# peripherals.net
KiCad netlist of a schematic drawn in Altium Designer
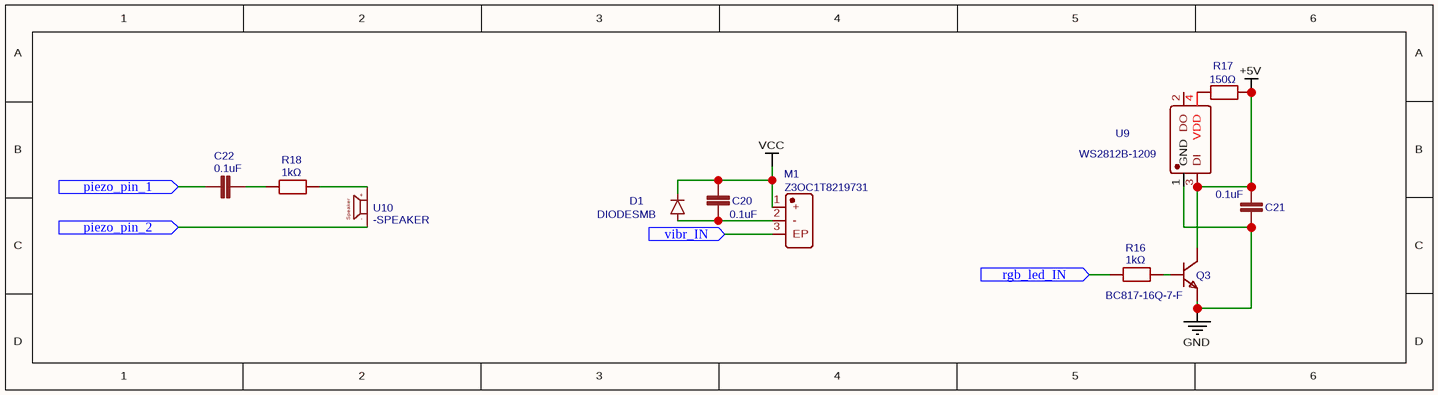
[diagram p0: peripherals.schdoc]

(export (version "E")
  (design (tool "Eeschema 10.0.6"))
  (components
    (comp (ref "C20")
      (value "0.1uF")
      (description "CAP-00810")
      (fields (field (name "CONTRIBUTOR") "SparkFun"))
      (libsource (lib "altium-import") (part "root_0_0.1uF_"))
    )
    (comp (ref "C21")
      (value "0.1uF")
      (description "CAP-00810")
      (fields (field (name "CONTRIBUTOR") "SparkFun"))
      (libsource (lib "altium-import") (part "root_0_0.1uF_"))
    )
    (comp (ref "C22")
      (value "0.1uF")
      (description "CAP-00810")
      (fields (field (name "CONTRIBUTOR") "SparkFun"))
      (libsource (lib "altium-import") (part "root_1_0.1uF_"))
    )
    (comp (ref "D1")
      (value "DIODESMB")
      (description "Diode")
      (fields (field (name "CONTRIBUTOR") "SparkFun"))
      (libsource (lib "altium-import") (part "root_1_DIODESMB_"))
    )
    (comp (ref "M1")
      (value "Z3OC1T8219731")
      (fields (field (name "BOM_SUPPLIER PART") "C2894731") (field (name "CONTRIBUTOR") "LCSC"))
      (libsource (lib "altium-import") (part "root_0_Z3OC1T8219731_"))
    )
    (comp (ref "Q3")
      (value "BC817-16Q-7-F")
      (fields (field (name "BOM_SUPPLIER PART") "C526459") (field (name "CONTRIBUTOR") "LCSC"))
      (libsource (lib "altium-import") (part "root_0_BC817-16Q-7-F_"))
    )
    (comp (ref "R16")
      (value "1kΩ")
      (fields
        (field (name "BOM_SUPPLIER PART") "C525388")
        (field (name "BOM_MANUFACTURER PART") "TCTR0603F47K0F3960T")
        (field (name "CONTRIBUTOR") "LCSC")
      )
      (libsource (lib "altium-import") (part "root_2_1kΩ_"))
    )
    (comp (ref "R17")
      (value "150Ω")
      (fields
        (field (name "BOM_SUPPLIER PART") "C525388")
        (field (name "BOM_MANUFACTURER PART") "TCTR0603F47K0F3960T")
        (field (name "CONTRIBUTOR") "LCSC")
      )
      (libsource (lib "altium-import") (part "root_0_150Ω_"))
    )
    (comp (ref "R18")
      (value "1kΩ")
      (fields
        (field (name "BOM_SUPPLIER PART") "C525388")
        (field (name "BOM_MANUFACTURER PART") "TCTR0603F47K0F3960T")
        (field (name "CONTRIBUTOR") "LCSC")
      )
      (libsource (lib "altium-import") (part "root_2_1kΩ_"))
    )
    (comp (ref "U9")
      (value "WS2812B-1209")
      (fields (field (name "BOM_SUPPLIER PART") "C2835111") (field (name "CONTRIBUTOR") "LCSC"))
      (libsource (lib "altium-import") (part "root_1_WS2812B-1209_"))
    )
    (comp (ref "U10") (value "-SPEAKER") (libsource (lib "altium-import") (part "root_1_-SPEAKER_")))
  )
  (nets
    (net (code "1") (name "+5V") (class "Default")
      (node (ref "C21") (pin "1") (pinfunction "1_1") (pintype "passive"))
      (node (ref "Q3") (pin "3") (pinfunction "C_3") (pintype "passive"))
      (node (ref "R17") (pin "2") (pinfunction "2_2") (pintype "passive"))
      (node (ref "U9") (pin "3") (pinfunction "DI_3") (pintype "passive"))
    )
    (net (code "2") (name "/piezo_pin_1") (class "Default")
      (node (ref "C22") (pin "1") (pinfunction "1_1") (pintype "passive"))
    )
    (net (code "3") (name "/piezo_pin_2") (class "Default")
      (node (ref "U10") (pin "NEG") (pinfunction "NEG_NEG") (pintype "passive"))
    )
    (net (code "4") (name "/rgb_led_IN") (class "Default")
      (node (ref "R16") (pin "2") (pinfunction "2_2") (pintype "passive"))
    )
    (net (code "5") (name "/vibr_IN") (class "Default")
      (node (ref "M1") (pin "3") (pinfunction "EP_3") (pintype "passive"))
    )
    (net (code "6") (name "GND") (class "Default")
      (node (ref "C21") (pin "2") (pinfunction "2_2") (pintype "passive"))
      (node (ref "Q3") (pin "2") (pinfunction "E_2") (pintype "passive"))
      (node (ref "U9") (pin "1") (pinfunction "GND_1") (pintype "passive"))
    )
    (net (code "7") (name "Net-(C22-Pad2)") (class "Default")
      (node (ref "C22") (pin "2") (pinfunction "2_2") (pintype "passive"))
      (node (ref "R18") (pin "2") (pinfunction "2_2") (pintype "passive"))
    )
    (net (code "8") (name "Net-(M1--)") (class "Default")
      (node (ref "C20") (pin "2") (pinfunction "2_2") (pintype "passive"))
      (node (ref "D1") (pin "A") (pinfunction "A_A") (pintype "passive"))
      (node (ref "M1") (pin "2") (pinfunction "-_2") (pintype "passive"))
    )
    (net (code "9") (name "Net-(Q3-B)") (class "Default")
      (node (ref "Q3") (pin "1") (pinfunction "B_1") (pintype "passive"))
      (node (ref "R16") (pin "1") (pinfunction "1_1") (pintype "passive"))
    )
    (net (code "10") (name "Net-(R18-Pad1)") (class "Default")
      (node (ref "R18") (pin "1") (pinfunction "1_1") (pintype "passive"))
      (node (ref "U10") (pin "POS") (pinfunction "POS_POS") (pintype "passive"))
    )
    (net (code "11") (name "Net-(U9-VDD)") (class "Default")
      (node (ref "R17") (pin "1") (pinfunction "1_1") (pintype "passive"))
      (node (ref "U9") (pin "4") (pinfunction "VDD_4") (pintype "passive"))
    )
    (net (code "12") (name "VCC") (class "Default")
      (node (ref "C20") (pin "1") (pinfunction "1_1") (pintype "passive"))
      (node (ref "D1") (pin "C") (pinfunction "C_C") (pintype "passive"))
      (node (ref "M1") (pin "1") (pinfunction "+_1") (pintype "passive"))
    )
    (net (code "13") (name "unconnected-(U9-DO-Pad2)") (class "Default")
      (node (ref "U9") (pin "2") (pinfunction "DO_2") (pintype "passive"))
    )
  )
)
